# Antenna_Board_v2.net
KiCad netlist of a schematic drawn in EAGLE
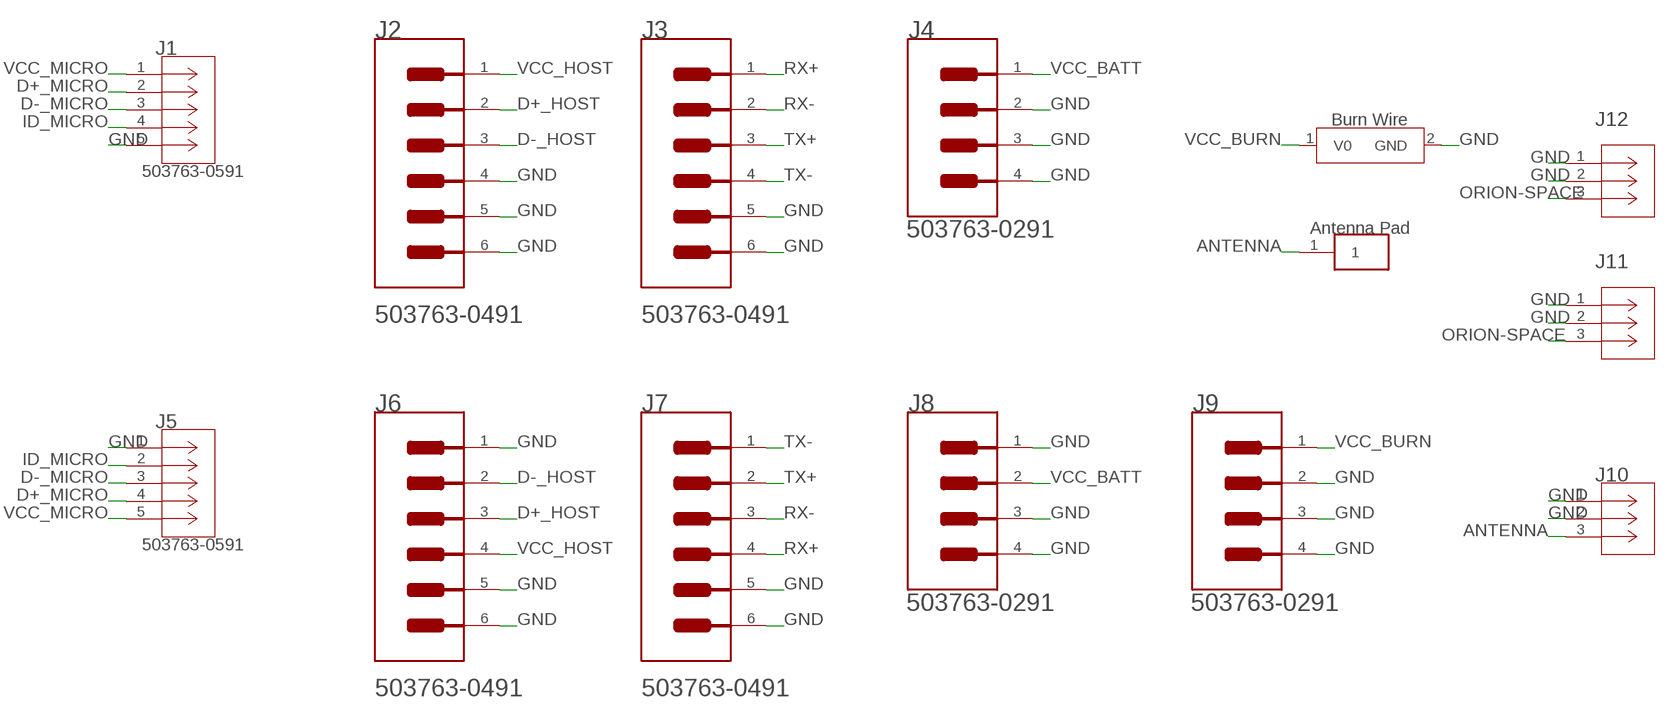
[diagram p0: schematic, sheet 1]

(export (version "E")
  (design (tool "Eeschema 10.0.6"))
  (components
    (comp (ref "J1")
      (value "503763-0591")
      (footprint "eagle-import:CONN_5037630591_MOL")
      (fields (field (name "COPYRIGHT") "Copyright (C) 2018 Accelerated Designs. All rights reserved"))
      (libsource (lib "eagle-import") (part "503763-0591"))
    )
    (comp (ref "J2")
      (value "MOLEX_503763-0491MOLEX_503763-0491_0_0")
      (footprint "eagle-import:MOLEX_503763-0491_0")
      (fields
        (field (name "DIGIKEY_PART_NUMBER") "WM10655CT-ND")
        (field (name "MF") "Molex")
        (field (name "MOUSER_PART_NUMBER") "538-503763-0491")
      )
      (libsource (lib "eagle-import") (part "MOLEX_503763-0491MOLEX_503763-0491_0_0"))
    )
    (comp (ref "J3")
      (value "MOLEX_503763-0491MOLEX_503763-0491_0_0")
      (footprint "eagle-import:MOLEX_503763-0491_0")
      (fields
        (field (name "DIGIKEY_PART_NUMBER") "WM10655CT-ND")
        (field (name "MF") "Molex")
        (field (name "MOUSER_PART_NUMBER") "538-503763-0491")
      )
      (libsource (lib "eagle-import") (part "MOLEX_503763-0491MOLEX_503763-0491_0_0"))
    )
    (comp (ref "J4")
      (value "MOLEX_503763-0291MOLEX_503763-0291_0_0")
      (footprint "eagle-import:MOLEX_503763-0291_0")
      (fields
        (field (name "DIGIKEY_PART_NUMBER") "WM10654CT-ND")
        (field (name "MF") "Molex")
        (field (name "MOUSER_PART_NUMBER") "538-503763-0291")
      )
      (libsource (lib "eagle-import") (part "MOLEX_503763-0291MOLEX_503763-0291_0_0"))
    )
    (comp (ref "J5")
      (value "503763-0591")
      (footprint "eagle-import:CONN_5037630591_MOL")
      (fields (field (name "COPYRIGHT") "Copyright (C) 2018 Accelerated Designs. All rights reserved"))
      (libsource (lib "eagle-import") (part "503763-0591"))
    )
    (comp (ref "J6")
      (value "MOLEX_503763-0491MOLEX_503763-0491_0_0")
      (footprint "eagle-import:MOLEX_503763-0491_0")
      (fields
        (field (name "DIGIKEY_PART_NUMBER") "WM10655CT-ND")
        (field (name "MF") "Molex")
        (field (name "MOUSER_PART_NUMBER") "538-503763-0491")
      )
      (libsource (lib "eagle-import") (part "MOLEX_503763-0491MOLEX_503763-0491_0_0"))
    )
    (comp (ref "J7")
      (value "MOLEX_503763-0491MOLEX_503763-0491_0_0")
      (footprint "eagle-import:MOLEX_503763-0491_0")
      (fields
        (field (name "DIGIKEY_PART_NUMBER") "WM10655CT-ND")
        (field (name "MF") "Molex")
        (field (name "MOUSER_PART_NUMBER") "538-503763-0491")
      )
      (libsource (lib "eagle-import") (part "MOLEX_503763-0491MOLEX_503763-0491_0_0"))
    )
    (comp (ref "J8")
      (value "MOLEX_503763-0291MOLEX_503763-0291_0_0")
      (footprint "eagle-import:MOLEX_503763-0291_0")
      (fields
        (field (name "DIGIKEY_PART_NUMBER") "WM10654CT-ND")
        (field (name "MF") "Molex")
        (field (name "MOUSER_PART_NUMBER") "538-503763-0291")
      )
      (libsource (lib "eagle-import") (part "MOLEX_503763-0291MOLEX_503763-0291_0_0"))
    )
    (comp (ref "J9")
      (value "MOLEX_503763-0291MOLEX_503763-0291_0_0")
      (footprint "eagle-import:MOLEX_503763-0291_0")
      (fields
        (field (name "DIGIKEY_PART_NUMBER") "WM10654CT-ND")
        (field (name "MF") "Molex")
        (field (name "MOUSER_PART_NUMBER") "538-503763-0291")
      )
      (libsource (lib "eagle-import") (part "MOLEX_503763-0291MOLEX_503763-0291_0_0"))
    )
    (comp (ref "J10")
      (value "U.FL-R-SMT-1(01)")
      (footprint "eagle-import:CONN_-SMT-1(01)")
      (fields (field (name "COPYRIGHT") "Copyright (C) 2018 Accelerated Designs. All rights reserved"))
      (libsource (lib "eagle-import") (part "U.FL-R-SMT-1(01)_U.FL-R-SMT-1(01)"))
    )
    (comp (ref "J11")
      (value "U.FL-R-SMT-1(01)")
      (footprint "eagle-import:CONN_-SMT-1(01)")
      (fields (field (name "COPYRIGHT") "Copyright (C) 2018 Accelerated Designs. All rights reserved"))
      (libsource (lib "eagle-import") (part "U.FL-R-SMT-1(01)"))
    )
    (comp (ref "J12")
      (value "U.FL-R-SMT-1(01)")
      (footprint "eagle-import:CONN_-SMT-1(01)")
      (fields (field (name "COPYRIGHT") "Copyright (C) 2018 Accelerated Designs. All rights reserved"))
      (libsource (lib "eagle-import") (part "U.FL-R-SMT-1(01)"))
    )
    (comp (ref "U$2")
      (value "ANTENNA_PAD")
      (footprint "eagle-import:ANTENNA_PAD")
      (libsource (lib "eagle-import") (part "ANTENNA_PAD"))
    )
    (comp (ref "U$3")
      (value "BURNWIRE")
      (footprint "eagle-import:BURNWIRE")
      (libsource (lib "eagle-import") (part "BURNWIRE"))
    )
  )
  (nets
    (net (code "1") (name "/ANTENNA") (class "Default")
      (node (ref "J10") (pin "3") (pinfunction "3_3") (pintype "passive"))
      (node (ref "U$2") (pin "1") (pinfunction "1_1") (pintype "bidirectional"))
    )
    (net (code "2") (name "/D+_HOST") (class "Default")
      (node (ref "J2") (pin "2") (pinfunction "2_2") (pintype "passive"))
      (node (ref "J6") (pin "3") (pinfunction "3_3") (pintype "passive"))
    )
    (net (code "3") (name "/D+_MICRO") (class "Default")
      (node (ref "J1") (pin "2") (pinfunction "2_2") (pintype "passive"))
      (node (ref "J5") (pin "4") (pinfunction "4_4") (pintype "passive"))
    )
    (net (code "4") (name "/D-_HOST") (class "Default")
      (node (ref "J2") (pin "3") (pinfunction "3_3") (pintype "passive"))
      (node (ref "J6") (pin "2") (pinfunction "2_2") (pintype "passive"))
    )
    (net (code "5") (name "/D-_MICRO") (class "Default")
      (node (ref "J1") (pin "3") (pinfunction "3_3") (pintype "passive"))
      (node (ref "J5") (pin "3") (pinfunction "3_3") (pintype "passive"))
    )
    (net (code "6") (name "/GND") (class "Default")
      (node (ref "J1") (pin "5") (pinfunction "5_5") (pintype "passive"))
      (node (ref "J10") (pin "1") (pinfunction "1_1") (pintype "passive"))
      (node (ref "J10") (pin "2") (pinfunction "2_2") (pintype "passive"))
      (node (ref "J11") (pin "1") (pinfunction "1_1") (pintype "passive"))
      (node (ref "J11") (pin "2") (pinfunction "2_2") (pintype "passive"))
      (node (ref "J12") (pin "1") (pinfunction "1_1") (pintype "passive"))
      (node (ref "J12") (pin "2") (pinfunction "2_2") (pintype "passive"))
      (node (ref "J2") (pin "4") (pinfunction "4_4") (pintype "passive"))
      (node (ref "J2") (pin "5") (pinfunction "MNT_1_5") (pintype "passive"))
      (node (ref "J2") (pin "6") (pinfunction "MNT_2_6") (pintype "passive"))
      (node (ref "J3") (pin "5") (pinfunction "MNT_1_5") (pintype "passive"))
      (node (ref "J3") (pin "6") (pinfunction "MNT_2_6") (pintype "passive"))
      (node (ref "J4") (pin "2") (pinfunction "2_2") (pintype "bidirectional"))
      (node (ref "J4") (pin "3") (pinfunction "MNT_1_3") (pintype "bidirectional"))
      (node (ref "J4") (pin "4") (pinfunction "MNT_2_4") (pintype "bidirectional"))
      (node (ref "J5") (pin "1") (pinfunction "1_1") (pintype "passive"))
      (node (ref "J6") (pin "1") (pinfunction "1_1") (pintype "passive"))
      (node (ref "J6") (pin "5") (pinfunction "MNT_1_5") (pintype "passive"))
      (node (ref "J6") (pin "6") (pinfunction "MNT_2_6") (pintype "passive"))
      (node (ref "J7") (pin "5") (pinfunction "MNT_1_5") (pintype "passive"))
      (node (ref "J7") (pin "6") (pinfunction "MNT_2_6") (pintype "passive"))
      (node (ref "J8") (pin "1") (pinfunction "1_1") (pintype "bidirectional"))
      (node (ref "J8") (pin "3") (pinfunction "MNT_1_3") (pintype "bidirectional"))
      (node (ref "J8") (pin "4") (pinfunction "MNT_2_4") (pintype "bidirectional"))
      (node (ref "J9") (pin "2") (pinfunction "2_2") (pintype "bidirectional"))
      (node (ref "J9") (pin "3") (pinfunction "MNT_1_3") (pintype "bidirectional"))
      (node (ref "J9") (pin "4") (pinfunction "MNT_2_4") (pintype "bidirectional"))
      (node (ref "U$3") (pin "2") (pinfunction "GND_2") (pintype "bidirectional"))
    )
    (net (code "7") (name "/ID_MICRO") (class "Default")
      (node (ref "J1") (pin "4") (pinfunction "4_4") (pintype "passive"))
      (node (ref "J5") (pin "2") (pinfunction "2_2") (pintype "passive"))
    )
    (net (code "8") (name "/ORION-SPACE") (class "Default")
      (node (ref "J11") (pin "3") (pinfunction "3_3") (pintype "passive"))
      (node (ref "J12") (pin "3") (pinfunction "3_3") (pintype "passive"))
    )
    (net (code "9") (name "/RX+") (class "Default")
      (node (ref "J3") (pin "1") (pinfunction "1_1") (pintype "passive"))
      (node (ref "J7") (pin "4") (pinfunction "4_4") (pintype "passive"))
    )
    (net (code "10") (name "/RX-") (class "Default")
      (node (ref "J3") (pin "2") (pinfunction "2_2") (pintype "passive"))
      (node (ref "J7") (pin "3") (pinfunction "3_3") (pintype "passive"))
    )
    (net (code "11") (name "/TX+") (class "Default")
      (node (ref "J3") (pin "3") (pinfunction "3_3") (pintype "passive"))
      (node (ref "J7") (pin "2") (pinfunction "2_2") (pintype "passive"))
    )
    (net (code "12") (name "/TX-") (class "Default")
      (node (ref "J3") (pin "4") (pinfunction "4_4") (pintype "passive"))
      (node (ref "J7") (pin "1") (pinfunction "1_1") (pintype "passive"))
    )
    (net (code "13") (name "/VCC_BATT") (class "Default")
      (node (ref "J4") (pin "1") (pinfunction "1_1") (pintype "bidirectional"))
      (node (ref "J8") (pin "2") (pinfunction "2_2") (pintype "bidirectional"))
    )
    (net (code "14") (name "/VCC_BURN") (class "Default")
      (node (ref "J9") (pin "1") (pinfunction "1_1") (pintype "bidirectional"))
      (node (ref "U$3") (pin "1") (pinfunction "V0_1") (pintype "bidirectional"))
    )
    (net (code "15") (name "/VCC_HOST") (class "Default")
      (node (ref "J2") (pin "1") (pinfunction "1_1") (pintype "passive"))
      (node (ref "J6") (pin "4") (pinfunction "4_4") (pintype "passive"))
    )
    (net (code "16") (name "/VCC_MICRO") (class "Default")
      (node (ref "J1") (pin "1") (pinfunction "1_1") (pintype "passive"))
      (node (ref "J5") (pin "5") (pinfunction "5_5") (pintype "passive"))
    )
  )
)
